# RB01.net
KiCad netlist of a schematic drawn in EAGLE
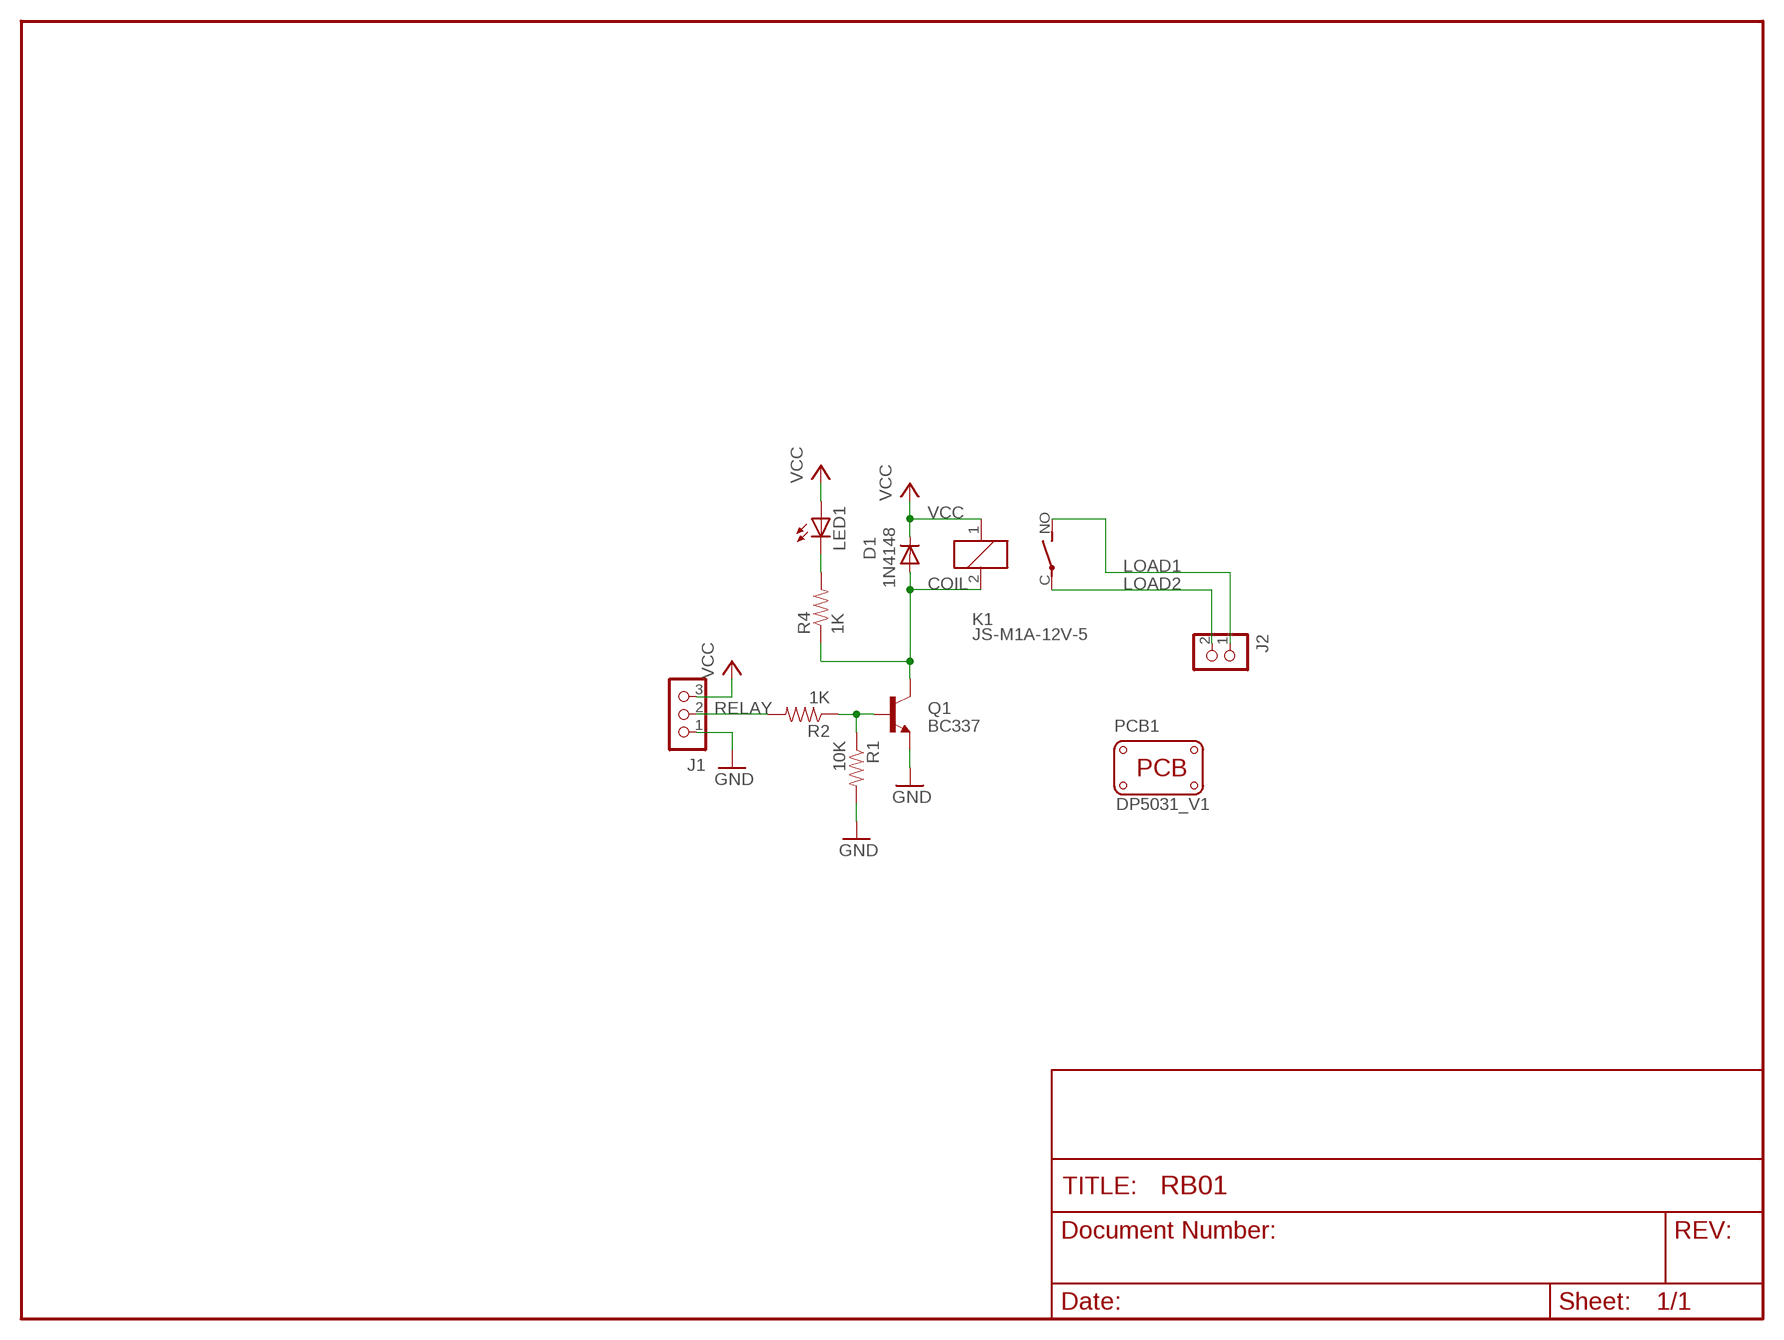
[diagram p0: schematic, sheet 1]

(export (version "E")
  (design (tool "Eeschema 10.0.6"))
  (components
    (comp (ref "D1")
      (value "1N4148")
      (footprint "eagle-import:DIODE-1N4148")
      (libsource (lib "eagle-import") (part "DIODE1N4148"))
    )
    (comp (ref "J1")
      (value "CON_TERMINAL_BLOCK_03-5MM")
      (footprint "eagle-import:TERMINAL_BLOCK_3P_5")
      (libsource (lib "eagle-import") (part "CON_TERMINAL_BLOCK_03-5MM"))
    )
    (comp (ref "J2")
      (value "CON_TERMINAL_BLOCK_02-5MM")
      (footprint "eagle-import:TERMINAL_BLOCK_2P_5")
      (libsource (lib "eagle-import") (part "CON_TERMINAL_BLOCK_02-5MM"))
    )
    (comp (ref "K1")
      (value "JS-M1A-12V-5")
      (footprint "eagle-import:JS-M1A")
      (fields (field (name "MPN") "JSM1A-12V-5"))
      (libsource (lib "eagle-import") (part "JS-M1A-12V-5"))
    )
    (comp (ref "LED1")
      (value "LED5MM")
      (footprint "eagle-import:LED5MM")
      (libsource (lib "eagle-import") (part "LED5MM"))
    )
    (comp (ref "PCB1")
      (value "PCB_DP_RECTANGLE-31X50")
      (footprint "eagle-import:DP5031_V1")
      (libsource (lib "eagle-import") (part "PCB_DP_RECTANGLE-31X50"))
    )
    (comp (ref "Q1")
      (value "BC337")
      (footprint "eagle-import:TO92")
      (libsource (lib "eagle-import") (part "BC337"))
    )
    (comp (ref "R1")
      (value "10K")
      (footprint "eagle-import:AXIAL-0.3")
      (libsource (lib "eagle-import") (part "RESISTORAXIAL-0.3"))
    )
    (comp (ref "R2")
      (value "1K")
      (footprint "eagle-import:AXIAL-0.3")
      (libsource (lib "eagle-import") (part "RESISTORAXIAL-0.3"))
    )
    (comp (ref "R4")
      (value "1K")
      (footprint "eagle-import:AXIAL-0.3")
      (libsource (lib "eagle-import") (part "RESISTORAXIAL-0.3"))
    )
  )
  (nets
    (net (code "1") (name "/COIL") (class "Default")
      (node (ref "D1") (pin "A") (pinfunction "A_A") (pintype "passive"))
      (node (ref "K1") (pin "2") (pinfunction "2_2") (pintype "passive"))
      (node (ref "Q1") (pin "3") (pinfunction "C_3") (pintype "passive"))
      (node (ref "R4") (pin "P$1") (pinfunction "1_P$1") (pintype "passive"))
    )
    (net (code "2") (name "/LOAD1") (class "Default")
      (node (ref "J2") (pin "1") (pinfunction "1_1") (pintype "passive"))
      (node (ref "K1") (pin "NO") (pinfunction "S_NO") (pintype "passive"))
    )
    (net (code "3") (name "/LOAD2") (class "Default")
      (node (ref "J2") (pin "2") (pinfunction "2_2") (pintype "passive"))
      (node (ref "K1") (pin "C") (pinfunction "P_C") (pintype "passive"))
    )
    (net (code "4") (name "/RELAY") (class "Default")
      (node (ref "J1") (pin "2") (pinfunction "2_2") (pintype "bidirectional"))
      (node (ref "R2") (pin "P$2") (pinfunction "2_P$2") (pintype "passive"))
    )
    (net (code "5") (name "GND") (class "Default")
      (node (ref "J1") (pin "1") (pinfunction "1_1") (pintype "bidirectional"))
      (node (ref "Q1") (pin "1") (pinfunction "E_1") (pintype "passive"))
      (node (ref "R1") (pin "P$2") (pinfunction "2_P$2") (pintype "passive"))
    )
    (net (code "6") (name "Net-(LED1-C)") (class "Default")
      (node (ref "LED1") (pin "K") (pinfunction "C_K") (pintype "passive"))
      (node (ref "R4") (pin "P$2") (pinfunction "2_P$2") (pintype "passive"))
    )
    (net (code "7") (name "Net-(Q1-B)") (class "Default")
      (node (ref "Q1") (pin "2") (pinfunction "B_2") (pintype "passive"))
      (node (ref "R1") (pin "P$1") (pinfunction "1_P$1") (pintype "passive"))
      (node (ref "R2") (pin "P$1") (pinfunction "1_P$1") (pintype "passive"))
    )
    (net (code "8") (name "VCC") (class "Default")
      (node (ref "D1") (pin "C") (pinfunction "C_C") (pintype "passive"))
      (node (ref "J1") (pin "3") (pinfunction "3_3") (pintype "bidirectional"))
      (node (ref "K1") (pin "1") (pinfunction "1_1") (pintype "passive"))
      (node (ref "LED1") (pin "A") (pinfunction "A_A") (pintype "passive"))
    )
  )
)
